# LM2596.net
KiCad netlist of a schematic drawn in Altium Designer
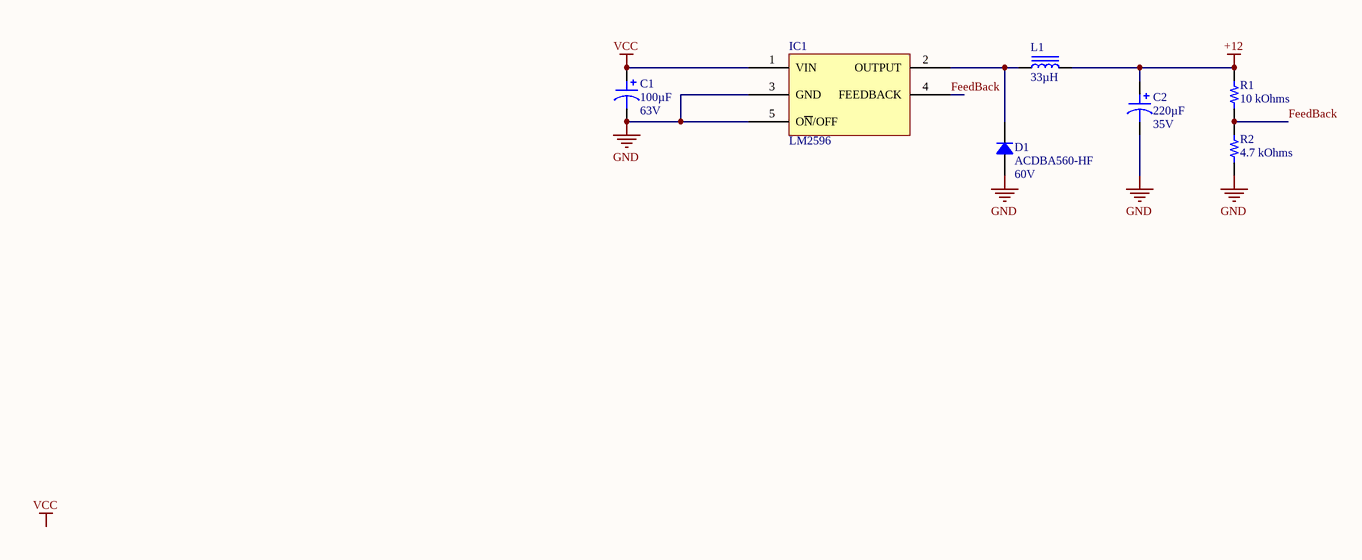
[diagram p0: LM2596.SchDoc]

(export (version "E")
  (design (tool "Eeschema 10.0.6"))
  (components
    (comp (ref "C1")
      (value "100µF")
      (footprint "CAP TH ALUM ELEC D8.00mm S3.50mm H12.50mm")
      (description "CAP ALUM 100UF 20% 63V RADIAL")
      (fields
        (field (name "PART NUMBER") "ECA-1JM101")
        (field (name "MANUFACTURER") "Panasonic Electronic Components")
        (field (name "VOLTAGE - RATED") "63V")
      )
      (libsource (lib "Celestial Altium Library - altium_library") (part "Polarised Capacitor"))
    )
    (comp (ref "C2")
      (value "220µF")
      (footprint "CAP TH ALUM ELEC D8.00mm S3.50mm H12.50mm")
      (description "CAP ALUM 220UF 20% 35V RADIAL")
      (fields
        (field (name "PART NUMBER") "ECA-1VM221BJ")
        (field (name "MANUFACTURER") "Panasonic Electronic Components")
        (field (name "VOLTAGE - RATED") "35V")
      )
      (libsource (lib "Celestial Altium Library - altium_library") (part "Polarised Capacitor"))
    )
    (comp (ref "D1")
      (value "ACDBA560-HF")
      (footprint "DO214AC SMA")
      (description "DIODE SCHOTTKY 60V 5A DO214AC")
      (fields
        (field (name "MANUFACTURER") "Comchip Technology")
        (field (name "VOLTAGE - DC REVERSE (VR) (MAX)") "60V")
      )
      (libsource (lib "Celestial Altium Library - altium_library") (part "Diode"))
    )
    (comp (ref "IC1") (value "LM2596") (footprint "DPAK") (libsource (lib "LM2596") (part "LM2596")))
    (comp (ref "L1")
      (value "33µH")
      (footprint "BOURNS SRR1280")
      (description "FIXED IND 33UH 3.5A 57 MOHM SMD")
      (fields (field (name "PART NUMBER") "SRR1280-330M") (field (name "MANUFACTURER") "Bourns Inc."))
      (libsource (lib "Celestial Altium Library - altium_library") (part "Inductor"))
    )
    (comp (ref "R1")
      (value "10 kOhms")
      (footprint "RES 0805_2012")
      (description "RES 10K OHM 0.1% 1/10W 0805")
      (fields
        (field (name "PART NUMBER") "RNCS0805BKE10K0")
        (field (name "MANUFACTURER") "Stackpole Electronics Inc")
      )
      (libsource (lib "Celestial Altium Library - altium_library") (part "Resistor"))
    )
    (comp (ref "R2")
      (value "4.7 kOhms")
      (footprint "RES 0805_2012")
      (description "CRGP 0805 4K7 1%")
      (fields
        (field (name "PART NUMBER") "CRGP0805F4K7")
        (field (name "MANUFACTURER") "TE Connectivity Passive Product")
      )
      (libsource (lib "Celestial Altium Library - altium_library") (part "Resistor"))
    )
  )
  (nets
    (net (code "1") (name "+12") (class "Default")
      (node (ref "C2") (pin "1") (pinfunction "1_1") (pintype "passive"))
      (node (ref "L1") (pin "2") (pinfunction "2_2") (pintype "passive"))
      (node (ref "R1") (pin "2") (pinfunction "2_2") (pintype "passive"))
    )
    (net (code "2") (name "/FeedBack") (class "Default")
      (node (ref "IC1") (pin "4") (pinfunction "FEEDBACK_4") (pintype "passive"))
      (node (ref "R1") (pin "1") (pinfunction "1_1") (pintype "passive"))
      (node (ref "R2") (pin "2") (pinfunction "2_2") (pintype "passive"))
    )
    (net (code "3") (name "GND") (class "Default")
      (node (ref "C1") (pin "2") (pinfunction "2_2") (pintype "passive"))
      (node (ref "C2") (pin "2") (pinfunction "2_2") (pintype "passive"))
      (node (ref "D1") (pin "1") (pinfunction "1_1") (pintype "passive"))
      (node (ref "IC1") (pin "3") (pinfunction "GND_3") (pintype "passive"))
      (node (ref "IC1") (pin "5") (pinfunction "O~{N}/OFF_5") (pintype "passive"))
      (node (ref "R2") (pin "1") (pinfunction "1_1") (pintype "passive"))
    )
    (net (code "4") (name "Net-(IC1-OUTPUT)") (class "Default")
      (node (ref "D1") (pin "2") (pinfunction "2_2") (pintype "passive"))
      (node (ref "IC1") (pin "2") (pinfunction "OUTPUT_2") (pintype "passive"))
      (node (ref "L1") (pin "1") (pinfunction "1_1") (pintype "passive"))
    )
    (net (code "5") (name "VCC") (class "Default")
      (node (ref "C1") (pin "1") (pinfunction "1_1") (pintype "passive"))
      (node (ref "IC1") (pin "1") (pinfunction "VIN_1") (pintype "passive"))
    )
  )
)
